# Power.net
KiCad netlist of a schematic drawn in Altium Designer
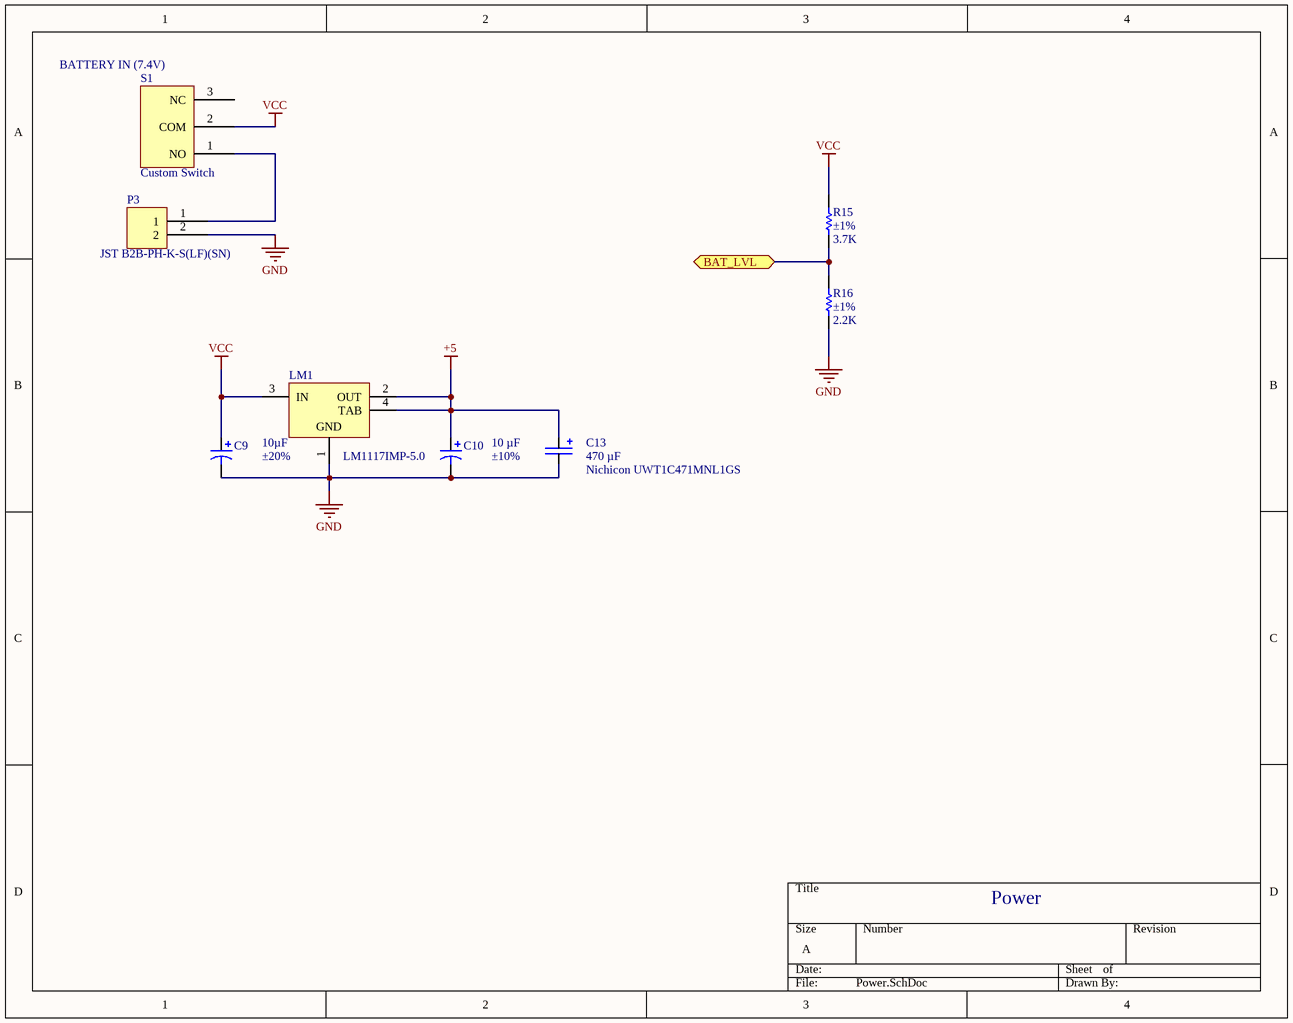
[diagram p0: Power.SchDoc]

(export (version "E")
  (design (tool "Eeschema 10.0.6"))
  (components
    (comp (ref "C9")
      (value "Kemet T491A106M006AT")
      (footprint "PCB-220579-1")
      (description "CAP TANT 10UF 6.3V 20% 1206")
      (fields (field (name "CAPACITANCE") "10µF") (field (name "CAPACITANCE TOLERANCE") "±20%"))
      (libsource (lib "CommunityVault") (part "CMP-220579-2"))
    )
    (comp (ref "C10")
      (value "Kemet T491B476K010AT")
      (footprint "CASE B")
      (description "Cap Tant Solid 47uF 10V B CASE 10% (3.5 X 2.8 X 1.9mm) SMD 3528-21 1 Ohm 125C Automotive T/R")
      (fields
        (field (name "CAPACITANCE") "10 µF")
        (field (name "CAPACITANCE TOLERANCE") "±10%")
        (field (name "MANUFACTURER PART NUMBER") "T491B476K010AT")
      )
      (libsource (lib "CommunityVault") (part "CMP-14388383-6"))
    )
    (comp (ref "C13")
      (value "Nichicon UWT1C471MNL1GS")
      (footprint "PCB-ohlypd69c1s53jj2mkj6-1")
      (description "8mm x 10mm 105deg Rohs=Yes 470uf 16-Volt Surface Mtg/Pkg Aluminum Electrolytic Cap")
      (fields
        (field (name "CAPACITANCE") "470 µF")
        (field (name "MANUFACTURER PART NUMBER") "UWT1C471MNL1GS")
      )
      (libsource (lib "CommunityVault") (part "CMP-f01f3916cccd2fd8-3"))
    )
    (comp (ref "LM1")
      (value "LM1117IMP-5.0")
      (footprint "MP04A_L")
      (description "800mA Low-Dropout Linear Regulator, 4-pin SOT-223, Pb-Free")
      (libsource (lib "Octopart library") (part "PM-REG-LM1086-SOT4"))
    )
    (comp (ref "P3")
      (value "JST B2B-PH-K-S(LF)(SN)")
      (footprint "PCB-gpdi66yn1jko56crxrq7-1")
      (description "PH Series 2 Position 2 mm Pitch Through Hole Top Entry Shrouded Header")
      (fields (field (name "MANUFACTURER PART NUMBER") "B2B-PH-K-S(LF)(SN)"))
      (libsource (lib "CommunityVault") (part "SYM-c32e0a272a631ce9-1"))
    )
    (comp (ref "R15")
      (value "Bourns CR0805-FX-4701GLF")
      (footprint "PCB-4097432-1")
      (description "Res Thick Film 0805 4.7K Ohm 1% 1/8W ±100ppm/°C Molded SMD SMD Paper Tape on Plastic Reel")
      (fields
        (field (name "MANUFACTURER PART NUMBER") "CR0805-FX-4701GLF")
        (field (name "RESISTANCE TOLERANCE") "±1%")
        (field (name "RESISTANCE") "3.7K")
      )
      (libsource (lib "CommunityVault") (part "CMP-97505e06006c4897-1"))
    )
    (comp (ref "R16")
      (value "Bourns CR0805-FX-4701GLF")
      (footprint "PCB-4097432-1")
      (description "Res Thick Film 0805 4.7K Ohm 1% 1/8W ±100ppm/°C Molded SMD SMD Paper Tape on Plastic Reel")
      (fields
        (field (name "MANUFACTURER PART NUMBER") "CR0805-FX-4701GLF")
        (field (name "RESISTANCE TOLERANCE") "±1%")
        (field (name "RESISTANCE") "2.2K")
      )
      (libsource (lib "CommunityVault") (part "CMP-97505e06006c4897-1"))
    )
    (comp (ref "S1")
      (value "Custom Switch")
      (footprint "PCB-tnt45azynpcpxvd4cmrw-1")
      (description "Switch Used in 2015's very small size robot")
      (libsource (lib "FavoritesLibrary") (part "SYM-s1vauaimn8qz55onjbfq-1"))
    )
  )
  (nets
    (net (code "1") (name "+5") (class "Default")
      (node (ref "C10") (pin "1") (pinfunction "1_1") (pintype "passive"))
      (node (ref "C13") (pin "P") (pinfunction "+_P") (pintype "passive"))
      (node (ref "LM1") (pin "2") (pinfunction "OUT_2") (pintype "power_in"))
      (node (ref "LM1") (pin "4") (pinfunction "TAB_4") (pintype "power_in"))
    )
    (net (code "2") (name "/BAT_LVL") (class "Default")
      (node (ref "R15") (pin "1") (pinfunction "1_1") (pintype "passive"))
      (node (ref "R16") (pin "2") (pinfunction "2_2") (pintype "passive"))
    )
    (net (code "3") (name "GND") (class "Default")
      (node (ref "C10") (pin "2") (pinfunction "2_2") (pintype "passive"))
      (node (ref "C13") (pin "M") (pinfunction "-_M") (pintype "passive"))
      (node (ref "C9") (pin "2") (pinfunction "2_2") (pintype "passive"))
      (node (ref "LM1") (pin "1") (pinfunction "GND_1") (pintype "power_in"))
      (node (ref "P3") (pin "2") (pinfunction "2_2") (pintype "passive"))
      (node (ref "R16") (pin "1") (pinfunction "1_1") (pintype "passive"))
    )
    (net (code "4") (name "Net-(S1-NO)") (class "Default")
      (node (ref "P3") (pin "1") (pinfunction "1_1") (pintype "passive"))
      (node (ref "S1") (pin "1") (pinfunction "NO_1") (pintype "passive"))
    )
    (net (code "5") (name "VCC") (class "Default")
      (node (ref "C9") (pin "1") (pinfunction "1_1") (pintype "passive"))
      (node (ref "LM1") (pin "3") (pinfunction "IN_3") (pintype "power_in"))
      (node (ref "R15") (pin "2") (pinfunction "2_2") (pintype "passive"))
      (node (ref "S1") (pin "2") (pinfunction "COM_2") (pintype "passive"))
    )
    (net (code "6") (name "unconnected-(S1-NC-Pad3)") (class "Default")
      (node (ref "S1") (pin "3") (pinfunction "NC_3") (pintype "passive"))
    )
  )
)
